# Power.net
KiCad netlist of a schematic drawn in Altium Designer
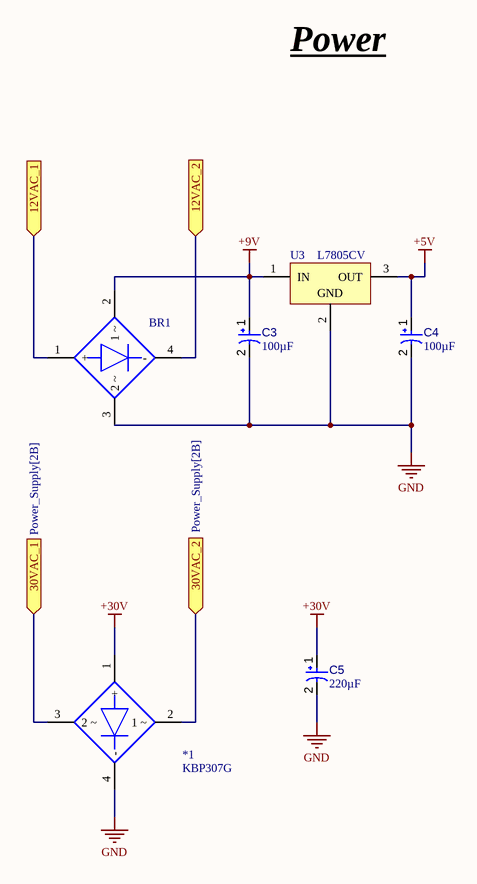
[diagram p0: Power.SchDoc]

(export (version "E")
  (design (tool "Eeschema 10.0.6"))
  (components
    (comp (ref "*1")
      (value "KBP307G")
      (footprint "KBP4")
      (description "3A, 1000V, Standard Bridge Rectifier")
      (libsource (lib "Konstantinos Psarras") (part "KBP307G-Symbol-1"))
    )
    (comp (ref "BR1")
      (value "GBU8D")
      (footprint "FP-127EL-MFG")
      (description "GBU8D Diode Rectifier Bridge Single 200V 8A 4-Pin Case GBU Rail")
      (libsource (lib "Altium Content Vault") (part "f9bc5961048aad4b77048d0b81a97d3"))
    )
    (comp (ref "C3")
      (value "100µF")
      (footprint "CAPPR55-250-1120X630X1220")
      (description "Aluminum Electrolytic Capacitor, 22 uF, +/- 20%, 100 V, -40 to 85 degC, 2-Pin THD, RoHS, Bulk")
      (fields (field (name "MANUFACTURER") "Panasonic") (field (name "TOLERANCE") "20%"))
      (libsource (lib "Konstantinos Psarras") (part "CAP-P-2"))
    )
    (comp (ref "C4")
      (value "100µF")
      (footprint "CAPPR55-250-1120X630X1220")
      (description "Aluminum Electrolytic Capacitor, 22 uF, +/- 20%, 100 V, -40 to 85 degC, 2-Pin THD, RoHS, Bulk")
      (fields (field (name "MANUFACTURER") "Panasonic") (field (name "TOLERANCE") "20%"))
      (libsource (lib "Konstantinos Psarras") (part "CAP-P-2"))
    )
    (comp (ref "C5")
      (value "220µF")
      (footprint "CAPPR65-500-1250X1000X1350")
      (description "Aluminum Electrolytic Capacitor, 220 uF, +/- 20%, 50 V, -40 to 85 degC, 2-Pin THD, RoHS, Bulk")
      (fields (field (name "MANUFACTURER") "Panasonic") (field (name "TOLERANCE") "20%"))
      (libsource (lib "Konstantinos Psarras") (part "CAP-P-2"))
    )
    (comp (ref "U3")
      (value "L7805CV")
      (footprint "TO220")
      (description "Positive Voltage Regulator, 5V, 3-Pin TO-220")
      (libsource (lib "Altium Content Vault") (part "PM-REG-L4940-SIL3"))
    )
  )
  (nets
    (net (code "1") (name "+5V") (class "Default")
      (node (ref "C4") (pin "1") (pinfunction "1_1") (pintype "passive"))
      (node (ref "U3") (pin "3") (pinfunction "OUT_3") (pintype "power_in"))
    )
    (net (code "2") (name "+9V") (class "Default")
      (node (ref "BR1") (pin "2") (pinfunction "1_~_2") (pintype "passive"))
      (node (ref "C3") (pin "1") (pinfunction "1_1") (pintype "passive"))
      (node (ref "U3") (pin "1") (pinfunction "IN_1") (pintype "power_in"))
    )
    (net (code "3") (name "+30V") (class "Default")
      (node (ref "*1") (pin "1") (pinfunction "+_1") (pintype "passive"))
      (node (ref "C5") (pin "1") (pinfunction "1_1") (pintype "passive"))
    )
    (net (code "4") (name "/12VAC_1") (class "Default")
      (node (ref "BR1") (pin "1") (pinfunction "+_1") (pintype "passive"))
    )
    (net (code "5") (name "/12VAC_2") (class "Default")
      (node (ref "BR1") (pin "4") (pinfunction "-_4") (pintype "passive"))
    )
    (net (code "6") (name "/30VAC_1") (class "Default")
      (node (ref "*1") (pin "3") (pinfunction "2_~_3") (pintype "passive"))
    )
    (net (code "7") (name "/30VAC_2") (class "Default")
      (node (ref "*1") (pin "2") (pinfunction "1_~_2") (pintype "passive"))
    )
    (net (code "8") (name "GND") (class "Default")
      (node (ref "*1") (pin "4") (pinfunction "-_4") (pintype "passive"))
      (node (ref "BR1") (pin "3") (pinfunction "2_~_3") (pintype "passive"))
      (node (ref "C3") (pin "2") (pinfunction "2_2") (pintype "passive"))
      (node (ref "C4") (pin "2") (pinfunction "2_2") (pintype "passive"))
      (node (ref "C5") (pin "2") (pinfunction "2_2") (pintype "passive"))
      (node (ref "U3") (pin "2") (pinfunction "GND_2") (pintype "power_in"))
    )
  )
)
